# PinguinoBase.net
KiCad netlist of a schematic drawn in EAGLE
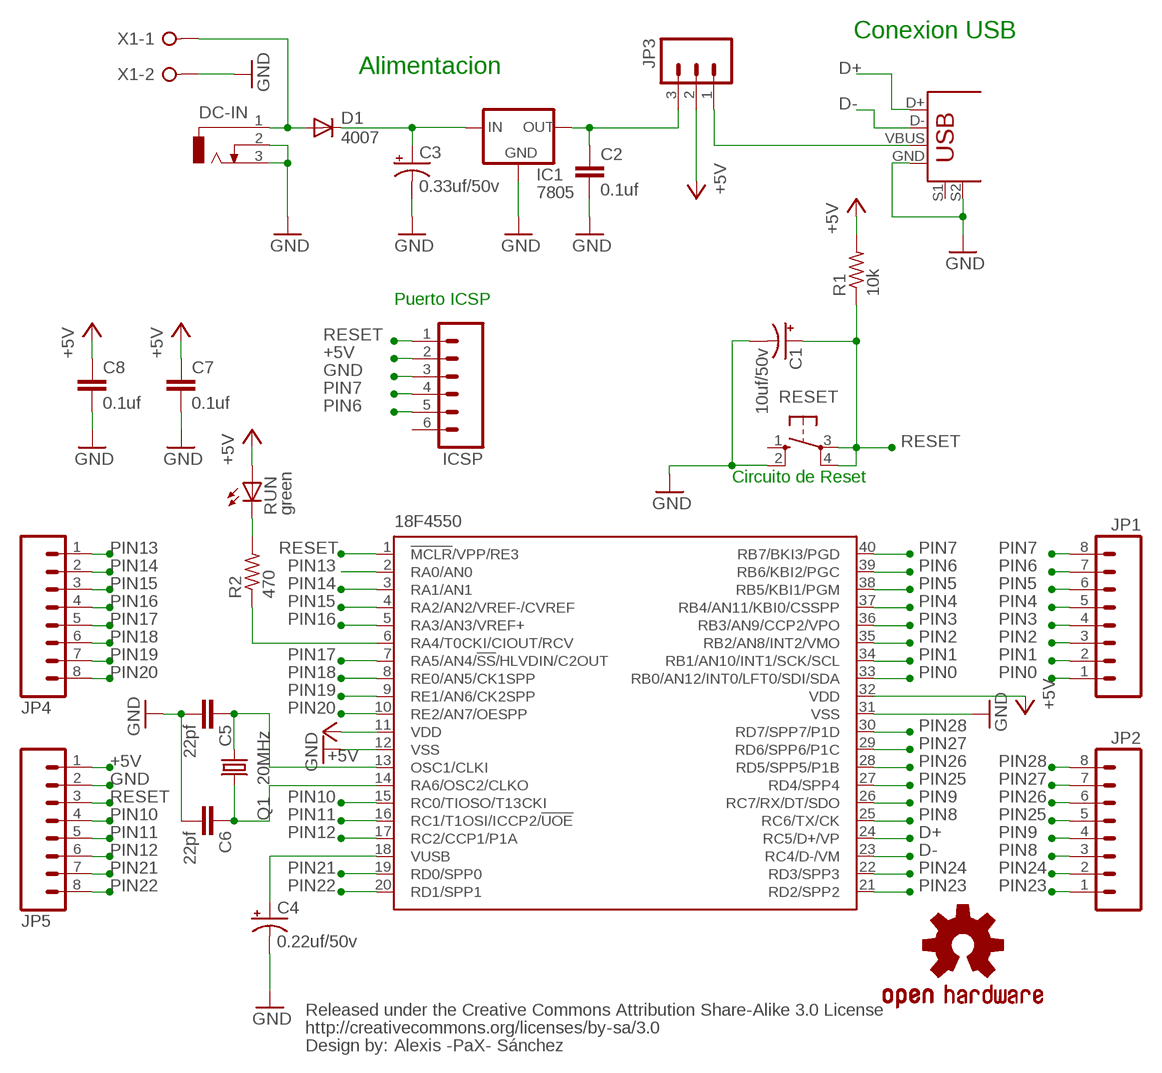
[diagram p0: schematic, sheet 1]

(export (version "E")
  (design (tool "Eeschema 10.0.6"))
  (components
    (comp (ref "18F4550")
      (value "PIC18F4550_40")
      (footprint "eagle-import:DIL40")
      (fields (field (name "MF") "MICROCHIP") (field (name "MPN") "PIC18F4550-I/P"))
      (libsource (lib "eagle-import") (part "PIC18F4_40550"))
    )
    (comp (ref "C1")
      (value "10uf/50v")
      (footprint "eagle-import:CPOL-RADIAL-10UF-25V")
      (libsource (lib "eagle-import") (part "CAP_POLPTH2"))
    )
    (comp (ref "C2")
      (value "0.1uf")
      (footprint "eagle-import:CAP-PTH-SMALL2")
      (libsource (lib "eagle-import") (part "CAPPTH2"))
    )
    (comp (ref "C3")
      (value "0.33uf/50v")
      (footprint "eagle-import:CPOL-RADIAL-10UF-25V")
      (libsource (lib "eagle-import") (part "CAP_POLPTH2"))
    )
    (comp (ref "C4")
      (value "0.22uf/50v")
      (footprint "eagle-import:CPOL-RADIAL-10UF-25V")
      (libsource (lib "eagle-import") (part "CAP_POLPTH2"))
    )
    (comp (ref "C5")
      (value "22pf")
      (footprint "eagle-import:CAP-PTH-SMALL2")
      (libsource (lib "eagle-import") (part "CAPPTH2"))
    )
    (comp (ref "C6")
      (value "22pf")
      (footprint "eagle-import:CAP-PTH-SMALL2")
      (libsource (lib "eagle-import") (part "CAPPTH2"))
    )
    (comp (ref "C7")
      (value "0.1uf")
      (footprint "eagle-import:CAP-PTH-SMALL2")
      (libsource (lib "eagle-import") (part "CAPPTH2"))
    )
    (comp (ref "C8")
      (value "0.1uf")
      (footprint "eagle-import:CAP-PTH-SMALL2")
      (libsource (lib "eagle-import") (part "CAPPTH2"))
    )
    (comp (ref "CC_TEXT1")
      (value "CREATIVE_COMMONS")
      (footprint "eagle-import:CREATIVE_COMMONS")
      (libsource (lib "eagle-import") (part "CREATIVE_COMMONS"))
    )
    (comp (ref "D1")
      (value "4007")
      (footprint "eagle-import:DO35-7")
      (libsource (lib "eagle-import") (part "1N4148DO35-7"))
    )
    (comp (ref "DC-IN")
      (value "DCJ0303")
      (footprint "eagle-import:DCJ0303")
      (libsource (lib "eagle-import") (part "DCJ0303"))
    )
    (comp (ref "IC1")
      (value "7805")
      (footprint "eagle-import:78XXL")
      (libsource (lib "eagle-import") (part "78XXL"))
    )
    (comp (ref "ICSP")
      (value "M06LONGPADS")
      (footprint "eagle-import:1X06_LONGPADS")
      (libsource (lib "eagle-import") (part "M06LONGPADS"))
    )
    (comp (ref "JP1")
      (value "M08LONGPADS")
      (footprint "eagle-import:1X08_LONGPADS")
      (libsource (lib "eagle-import") (part "M08LONGPADS"))
    )
    (comp (ref "JP2")
      (value "M08LONGPADS")
      (footprint "eagle-import:1X08_LONGPADS")
      (libsource (lib "eagle-import") (part "M08LONGPADS"))
    )
    (comp (ref "JP3")
      (value "M03LONGPADS")
      (footprint "eagle-import:1X03_LONGPADS")
      (libsource (lib "eagle-import") (part "M03LONGPADS"))
    )
    (comp (ref "JP4")
      (value "M08LONGPADS")
      (footprint "eagle-import:1X08_LONGPADS")
      (libsource (lib "eagle-import") (part "M08LONGPADS"))
    )
    (comp (ref "JP5")
      (value "M08LONGPADS")
      (footprint "eagle-import:1X08_LONGPADS")
      (libsource (lib "eagle-import") (part "M08LONGPADS"))
    )
    (comp (ref "LOGO1")
      (value "OSHW-LOGOL")
      (footprint "eagle-import:OSHW-LOGO-L")
      (libsource (lib "eagle-import") (part "OSHW-LOGOL"))
    )
    (comp (ref "Q1")
      (value "20MHz")
      (footprint "eagle-import:HC49U-V")
      (libsource (lib "eagle-import") (part "CRYSTALHC49U-V"))
    )
    (comp (ref "R1")
      (value "10k")
      (footprint "eagle-import:0207_7")
      (libsource (lib "eagle-import") (part "R-US_0207/7"))
    )
    (comp (ref "R2")
      (value "470")
      (footprint "eagle-import:0207_7")
      (libsource (lib "eagle-import") (part "R-US_0207/7"))
    )
    (comp (ref "RESET")
      (value "10-XX")
      (footprint "eagle-import:B3F-10XX")
      (fields (field (name "MPN") "B3F-1000"))
      (libsource (lib "eagle-import") (part "10-XX"))
    )
    (comp (ref "RUN")
      (value "green")
      (footprint "eagle-import:LED3MM")
      (libsource (lib "eagle-import") (part "LED3MM"))
    )
    (comp (ref "USB")
      (value "USB+SHIELD")
      (footprint "eagle-import:USB-B-PTH")
      (libsource (lib "eagle-import") (part "USB+SHIELD"))
    )
    (comp (ref "X1")
      (value "W237-02P")
      (footprint "eagle-import:W237-132")
      (libsource (lib "eagle-import") (part "W237-02P"))
    )
  )
  (nets
    (net (code "1") (name "+5V") (class "Default")
      (node (ref "18F4550") (pin "11") (pinfunction "VDD_11") (pintype "power_in"))
      (node (ref "18F4550") (pin "32") (pinfunction "VDD_32") (pintype "power_in"))
      (node (ref "C7") (pin "1") (pinfunction "1_1") (pintype "passive"))
      (node (ref "C8") (pin "1") (pinfunction "1_1") (pintype "passive"))
      (node (ref "ICSP") (pin "2") (pinfunction "2_2") (pintype "passive"))
      (node (ref "JP3") (pin "2") (pinfunction "2_2") (pintype "passive"))
      (node (ref "JP5") (pin "1") (pinfunction "1_1") (pintype "passive"))
      (node (ref "R1") (pin "2") (pinfunction "2_2") (pintype "passive"))
      (node (ref "RUN") (pin "A") (pinfunction "A_A") (pintype "passive"))
    )
    (net (code "2") (name "/D+") (class "Default")
      (node (ref "18F4550") (pin "24") (pinfunction "RC5/D+/VP_24") (pintype "bidirectional"))
      (node (ref "USB") (pin "D+") (pinfunction "D+_D+") (pintype "bidirectional"))
    )
    (net (code "3") (name "/D-") (class "Default")
      (node (ref "18F4550") (pin "23") (pinfunction "RC4/D-/VM_23") (pintype "bidirectional"))
      (node (ref "USB") (pin "D-") (pinfunction "D-_D-") (pintype "bidirectional"))
    )
    (net (code "4") (name "/PIN0") (class "Default")
      (node (ref "18F4550") (pin "33") (pinfunction "RB0/AN12/INT0/LFT0/SDI/SDA_33") (pintype "bidirectional"))
      (node (ref "JP1") (pin "1") (pinfunction "1_1") (pintype "passive"))
    )
    (net (code "5") (name "/PIN1") (class "Default")
      (node (ref "18F4550") (pin "34") (pinfunction "RB1/AN10/INT1/SCK/SCL_34") (pintype "bidirectional"))
      (node (ref "JP1") (pin "2") (pinfunction "2_2") (pintype "passive"))
    )
    (net (code "6") (name "/PIN2") (class "Default")
      (node (ref "18F4550") (pin "35") (pinfunction "RB2/AN8/INT2/VMO_35") (pintype "bidirectional"))
      (node (ref "JP1") (pin "3") (pinfunction "3_3") (pintype "passive"))
    )
    (net (code "7") (name "/PIN3") (class "Default")
      (node (ref "18F4550") (pin "36") (pinfunction "RB3/AN9/CCP2/VPO_36") (pintype "bidirectional"))
      (node (ref "JP1") (pin "4") (pinfunction "4_4") (pintype "passive"))
    )
    (net (code "8") (name "/PIN4") (class "Default")
      (node (ref "18F4550") (pin "37") (pinfunction "RB4/AN11/KBI0/CSSPP_37") (pintype "bidirectional"))
      (node (ref "JP1") (pin "5") (pinfunction "5_5") (pintype "passive"))
    )
    (net (code "9") (name "/PIN5") (class "Default")
      (node (ref "18F4550") (pin "38") (pinfunction "RB5/KBI1/PGM_38") (pintype "bidirectional"))
      (node (ref "JP1") (pin "6") (pinfunction "6_6") (pintype "passive"))
    )
    (net (code "10") (name "/PIN6") (class "Default")
      (node (ref "18F4550") (pin "39") (pinfunction "RB6/KBI2/PGC_39") (pintype "bidirectional"))
      (node (ref "ICSP") (pin "5") (pinfunction "5_5") (pintype "passive"))
      (node (ref "JP1") (pin "7") (pinfunction "7_7") (pintype "passive"))
    )
    (net (code "11") (name "/PIN7") (class "Default")
      (node (ref "18F4550") (pin "40") (pinfunction "RB7/BKI3/PGD_40") (pintype "bidirectional"))
      (node (ref "ICSP") (pin "4") (pinfunction "4_4") (pintype "passive"))
      (node (ref "JP1") (pin "8") (pinfunction "8_8") (pintype "passive"))
    )
    (net (code "12") (name "/PIN8") (class "Default")
      (node (ref "18F4550") (pin "25") (pinfunction "RC6/TX/CK_25") (pintype "bidirectional"))
      (node (ref "JP2") (pin "3") (pinfunction "3_3") (pintype "passive"))
    )
    (net (code "13") (name "/PIN9") (class "Default")
      (node (ref "18F4550") (pin "26") (pinfunction "RC7/RX/DT/SDO_26") (pintype "bidirectional"))
      (node (ref "JP2") (pin "4") (pinfunction "4_4") (pintype "passive"))
    )
    (net (code "14") (name "/PIN10") (class "Default")
      (node (ref "18F4550") (pin "15") (pinfunction "RC0/TIOSO/T13CKI_15") (pintype "bidirectional"))
      (node (ref "JP5") (pin "4") (pinfunction "4_4") (pintype "passive"))
    )
    (net (code "15") (name "/PIN11") (class "Default")
      (node (ref "18F4550") (pin "16") (pinfunction "RC1/T1OSI/ICCP2/~{UOE}_16") (pintype "bidirectional"))
      (node (ref "JP5") (pin "5") (pinfunction "5_5") (pintype "passive"))
    )
    (net (code "16") (name "/PIN12") (class "Default")
      (node (ref "18F4550") (pin "17") (pinfunction "RC2/CCP1/P1A_17") (pintype "bidirectional"))
      (node (ref "JP5") (pin "6") (pinfunction "6_6") (pintype "passive"))
    )
    (net (code "17") (name "/PIN13") (class "Default")
      (node (ref "18F4550") (pin "2") (pinfunction "RA0/AN0_2") (pintype "bidirectional"))
      (node (ref "JP4") (pin "1") (pinfunction "1_1") (pintype "passive"))
    )
    (net (code "18") (name "/PIN14") (class "Default")
      (node (ref "18F4550") (pin "3") (pinfunction "RA1/AN1_3") (pintype "bidirectional"))
      (node (ref "JP4") (pin "2") (pinfunction "2_2") (pintype "passive"))
    )
    (net (code "19") (name "/PIN15") (class "Default")
      (node (ref "18F4550") (pin "4") (pinfunction "RA2/AN2/VREF-/CVREF_4") (pintype "bidirectional"))
      (node (ref "JP4") (pin "3") (pinfunction "3_3") (pintype "passive"))
    )
    (net (code "20") (name "/PIN16") (class "Default")
      (node (ref "18F4550") (pin "5") (pinfunction "RA3/AN3/VREF+_5") (pintype "bidirectional"))
      (node (ref "JP4") (pin "4") (pinfunction "4_4") (pintype "passive"))
    )
    (net (code "21") (name "/PIN17") (class "Default")
      (node (ref "18F4550") (pin "7") (pinfunction "RA5/AN4/~{SS}/HLVDIN/C2OUT_7") (pintype "bidirectional"))
      (node (ref "JP4") (pin "5") (pinfunction "5_5") (pintype "passive"))
    )
    (net (code "22") (name "/PIN18") (class "Default")
      (node (ref "18F4550") (pin "8") (pinfunction "RE0/AN5/CK1SPP_8") (pintype "bidirectional"))
      (node (ref "JP4") (pin "6") (pinfunction "6_6") (pintype "passive"))
    )
    (net (code "23") (name "/PIN19") (class "Default")
      (node (ref "18F4550") (pin "9") (pinfunction "RE1/AN6/CK2SPP_9") (pintype "bidirectional"))
      (node (ref "JP4") (pin "7") (pinfunction "7_7") (pintype "passive"))
    )
    (net (code "24") (name "/PIN20") (class "Default")
      (node (ref "18F4550") (pin "10") (pinfunction "RE2/AN7/OESPP_10") (pintype "bidirectional"))
      (node (ref "JP4") (pin "8") (pinfunction "8_8") (pintype "passive"))
    )
    (net (code "25") (name "/PIN21") (class "Default")
      (node (ref "18F4550") (pin "19") (pinfunction "RD0/SPP0_19") (pintype "bidirectional"))
      (node (ref "JP5") (pin "7") (pinfunction "7_7") (pintype "passive"))
    )
    (net (code "26") (name "/PIN22") (class "Default")
      (node (ref "18F4550") (pin "20") (pinfunction "RD1/SPP1_20") (pintype "bidirectional"))
      (node (ref "JP5") (pin "8") (pinfunction "8_8") (pintype "passive"))
    )
    (net (code "27") (name "/PIN23") (class "Default")
      (node (ref "18F4550") (pin "21") (pinfunction "RD2/SPP2_21") (pintype "bidirectional"))
      (node (ref "JP2") (pin "1") (pinfunction "1_1") (pintype "passive"))
    )
    (net (code "28") (name "/PIN24") (class "Default")
      (node (ref "18F4550") (pin "22") (pinfunction "RD3/SPP3_22") (pintype "bidirectional"))
      (node (ref "JP2") (pin "2") (pinfunction "2_2") (pintype "passive"))
    )
    (net (code "29") (name "/PIN25") (class "Default")
      (node (ref "18F4550") (pin "27") (pinfunction "RD4/SPP4_27") (pintype "bidirectional"))
      (node (ref "JP2") (pin "5") (pinfunction "5_5") (pintype "passive"))
    )
    (net (code "30") (name "/PIN26") (class "Default")
      (node (ref "18F4550") (pin "28") (pinfunction "RD5/SPP5/P1B_28") (pintype "bidirectional"))
      (node (ref "JP2") (pin "6") (pinfunction "6_6") (pintype "passive"))
    )
    (net (code "31") (name "/PIN27") (class "Default")
      (node (ref "18F4550") (pin "29") (pinfunction "RD6/SPP6/P1C_29") (pintype "bidirectional"))
      (node (ref "JP2") (pin "7") (pinfunction "7_7") (pintype "passive"))
    )
    (net (code "32") (name "/PIN28") (class "Default")
      (node (ref "18F4550") (pin "30") (pinfunction "RD7/SPP7/P1D_30") (pintype "bidirectional"))
      (node (ref "JP2") (pin "8") (pinfunction "8_8") (pintype "passive"))
    )
    (net (code "33") (name "/RESET") (class "Default")
      (node (ref "18F4550") (pin "1") (pinfunction "~{MCLR}/VPP/RE3_1") (pintype "input"))
      (node (ref "C1") (pin "1") (pinfunction "+_1") (pintype "passive"))
      (node (ref "ICSP") (pin "1") (pinfunction "1_1") (pintype "passive"))
      (node (ref "JP5") (pin "3") (pinfunction "3_3") (pintype "passive"))
      (node (ref "R1") (pin "1") (pinfunction "1_1") (pintype "passive"))
      (node (ref "RESET") (pin "3") (pinfunction "P_3") (pintype "passive"))
      (node (ref "RESET") (pin "4") (pinfunction "P1_4") (pintype "passive"))
    )
    (net (code "34") (name "GND") (class "Default")
      (node (ref "18F4550") (pin "12") (pinfunction "VSS_12") (pintype "power_in"))
      (node (ref "18F4550") (pin "31") (pinfunction "VSS_31") (pintype "power_in"))
      (node (ref "C1") (pin "2") (pinfunction "-_2") (pintype "passive"))
      (node (ref "C2") (pin "2") (pinfunction "2_2") (pintype "passive"))
      (node (ref "C3") (pin "2") (pinfunction "-_2") (pintype "passive"))
      (node (ref "C4") (pin "2") (pinfunction "-_2") (pintype "passive"))
      (node (ref "C5") (pin "2") (pinfunction "2_2") (pintype "passive"))
      (node (ref "C6") (pin "2") (pinfunction "2_2") (pintype "passive"))
      (node (ref "C7") (pin "2") (pinfunction "2_2") (pintype "passive"))
      (node (ref "C8") (pin "2") (pinfunction "2_2") (pintype "passive"))
      (node (ref "DC-IN") (pin "2") (pinfunction "2_2") (pintype "passive"))
      (node (ref "DC-IN") (pin "3") (pinfunction "3_3") (pintype "passive"))
      (node (ref "IC1") (pin "GND") (pinfunction "GND_GND") (pintype "input"))
      (node (ref "ICSP") (pin "3") (pinfunction "3_3") (pintype "passive"))
      (node (ref "JP5") (pin "2") (pinfunction "2_2") (pintype "passive"))
      (node (ref "RESET") (pin "2") (pinfunction "S1_2") (pintype "passive"))
      (node (ref "USB") (pin "GND") (pinfunction "GND_GND") (pintype "bidirectional"))
      (node (ref "USB") (pin "S2") (pinfunction "P$2_S2") (pintype "bidirectional"))
      (node (ref "X1") (pin "2") (pinfunction "KL_2") (pintype "passive"))
    )
    (net (code "35") (name "Net-(18F4550-OSC1{slash}CLKI)") (class "Default")
      (node (ref "18F4550") (pin "13") (pinfunction "OSC1/CLKI_13") (pintype "input"))
      (node (ref "C5") (pin "1") (pinfunction "1_1") (pintype "passive"))
      (node (ref "Q1") (pin "1") (pinfunction "1_1") (pintype "passive"))
    )
    (net (code "36") (name "Net-(18F4550-RA4{slash}T0CKI{slash}CIOUT{slash}RCV)") (class "Default")
      (node (ref "18F4550") (pin "6") (pinfunction "RA4/T0CKI/CIOUT/RCV_6") (pintype "bidirectional"))
      (node (ref "R2") (pin "1") (pinfunction "1_1") (pintype "passive"))
    )
    (net (code "37") (name "Net-(18F4550-RA6{slash}OSC2{slash}CLKO)") (class "Default")
      (node (ref "18F4550") (pin "14") (pinfunction "RA6/OSC2/CLKO_14") (pintype "output"))
      (node (ref "C6") (pin "1") (pinfunction "1_1") (pintype "passive"))
      (node (ref "Q1") (pin "2") (pinfunction "2_2") (pintype "passive"))
    )
    (net (code "38") (name "Net-(18F4550-VUSB)") (class "Default")
      (node (ref "18F4550") (pin "18") (pinfunction "VUSB_18") (pintype "bidirectional"))
      (node (ref "C4") (pin "1") (pinfunction "+_1") (pintype "passive"))
    )
    (net (code "39") (name "Net-(C2-Pad1)") (class "Default")
      (node (ref "C2") (pin "1") (pinfunction "1_1") (pintype "passive"))
      (node (ref "IC1") (pin "OUT") (pinfunction "OUT_OUT") (pintype "passive"))
      (node (ref "JP3") (pin "3") (pinfunction "3_3") (pintype "passive"))
    )
    (net (code "40") (name "Net-(C3-+)") (class "Default")
      (node (ref "C3") (pin "1") (pinfunction "+_1") (pintype "passive"))
      (node (ref "D1") (pin "C") (pinfunction "C_C") (pintype "passive"))
      (node (ref "IC1") (pin "IN") (pinfunction "IN_IN") (pintype "input"))
    )
    (net (code "41") (name "Net-(JP3-Pad1)") (class "Default")
      (node (ref "JP3") (pin "1") (pinfunction "1_1") (pintype "passive"))
      (node (ref "USB") (pin "VBUS") (pinfunction "VBUS_VBUS") (pintype "bidirectional"))
    )
    (net (code "42") (name "Net-(RUN-C)") (class "Default")
      (node (ref "R2") (pin "2") (pinfunction "2_2") (pintype "passive"))
      (node (ref "RUN") (pin "K") (pinfunction "C_K") (pintype "passive"))
    )
    (net (code "43") (name "Net-(X1A-KL)") (class "Default")
      (node (ref "D1") (pin "A") (pinfunction "A_A") (pintype "passive"))
      (node (ref "DC-IN") (pin "1") (pinfunction "1_1") (pintype "passive"))
      (node (ref "X1") (pin "1") (pinfunction "KL_1") (pintype "passive"))
    )
    (net (code "44") (name "unconnected-(ICSP-Pad6)") (class "Default")
      (node (ref "ICSP") (pin "6") (pinfunction "6_6") (pintype "passive"))
    )
    (net (code "45") (name "unconnected-(RESET-S-Pad1)") (class "Default")
      (node (ref "RESET") (pin "1") (pinfunction "S_1") (pintype "passive"))
    )
    (net (code "46") (name "unconnected-(USB-P$1-PadS1)") (class "Default")
      (node (ref "USB") (pin "S1") (pinfunction "P$1_S1") (pintype "bidirectional"))
    )
  )
)
